# 4P_JST-PH_EXT.net
KiCad netlist of a schematic drawn in Altium Designer
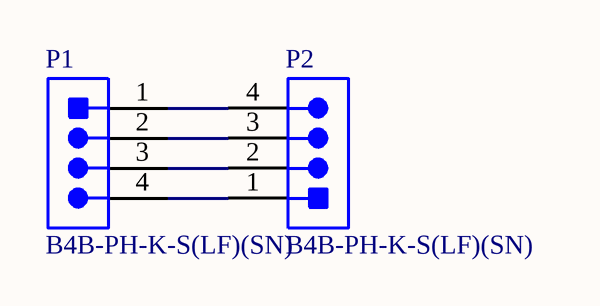
[diagram p0: 4P_JST-PH_EXT.SchDoc]

(export (version "E")
  (design (tool "Eeschema 10.0.6"))
  (components
    (comp (ref "P1")
      (value "B4B-PH-K-S(LF)(SN)")
      (footprint "JST-B4B-PH-K-S_V")
      (fields (field (name "MANUFACTURER") "JST"))
      (libsource (lib "Altium Content Vault") (part "CN-1P-M-R4"))
    )
    (comp (ref "P2")
      (value "B4B-PH-K-S(LF)(SN)")
      (footprint "JST-B4B-PH-K-S_V")
      (fields (field (name "MANUFACTURER") "JST"))
      (libsource (lib "") (part "CN-1P-M-R4_1"))
    )
  )
  (nets
    (net (code "1") (name "Net-(P1-Pad1)") (class "Default")
      (node (ref "P1") (pin "1") (pinfunction "1_1") (pintype "passive"))
      (node (ref "P2") (pin "4") (pinfunction "4_4") (pintype "passive"))
    )
    (net (code "2") (name "Net-(P1-Pad2)") (class "Default")
      (node (ref "P1") (pin "2") (pinfunction "2_2") (pintype "passive"))
      (node (ref "P2") (pin "3") (pinfunction "3_3") (pintype "passive"))
    )
    (net (code "3") (name "Net-(P1-Pad3)") (class "Default")
      (node (ref "P1") (pin "3") (pinfunction "3_3") (pintype "passive"))
      (node (ref "P2") (pin "2") (pinfunction "2_2") (pintype "passive"))
    )
    (net (code "4") (name "Net-(P1-Pad4)") (class "Default")
      (node (ref "P1") (pin "4") (pinfunction "4_4") (pintype "passive"))
      (node (ref "P2") (pin "1") (pinfunction "1_1") (pintype "passive"))
    )
  )
)
